# Backplane.net
KiCad netlist of a schematic drawn in Altium Designer
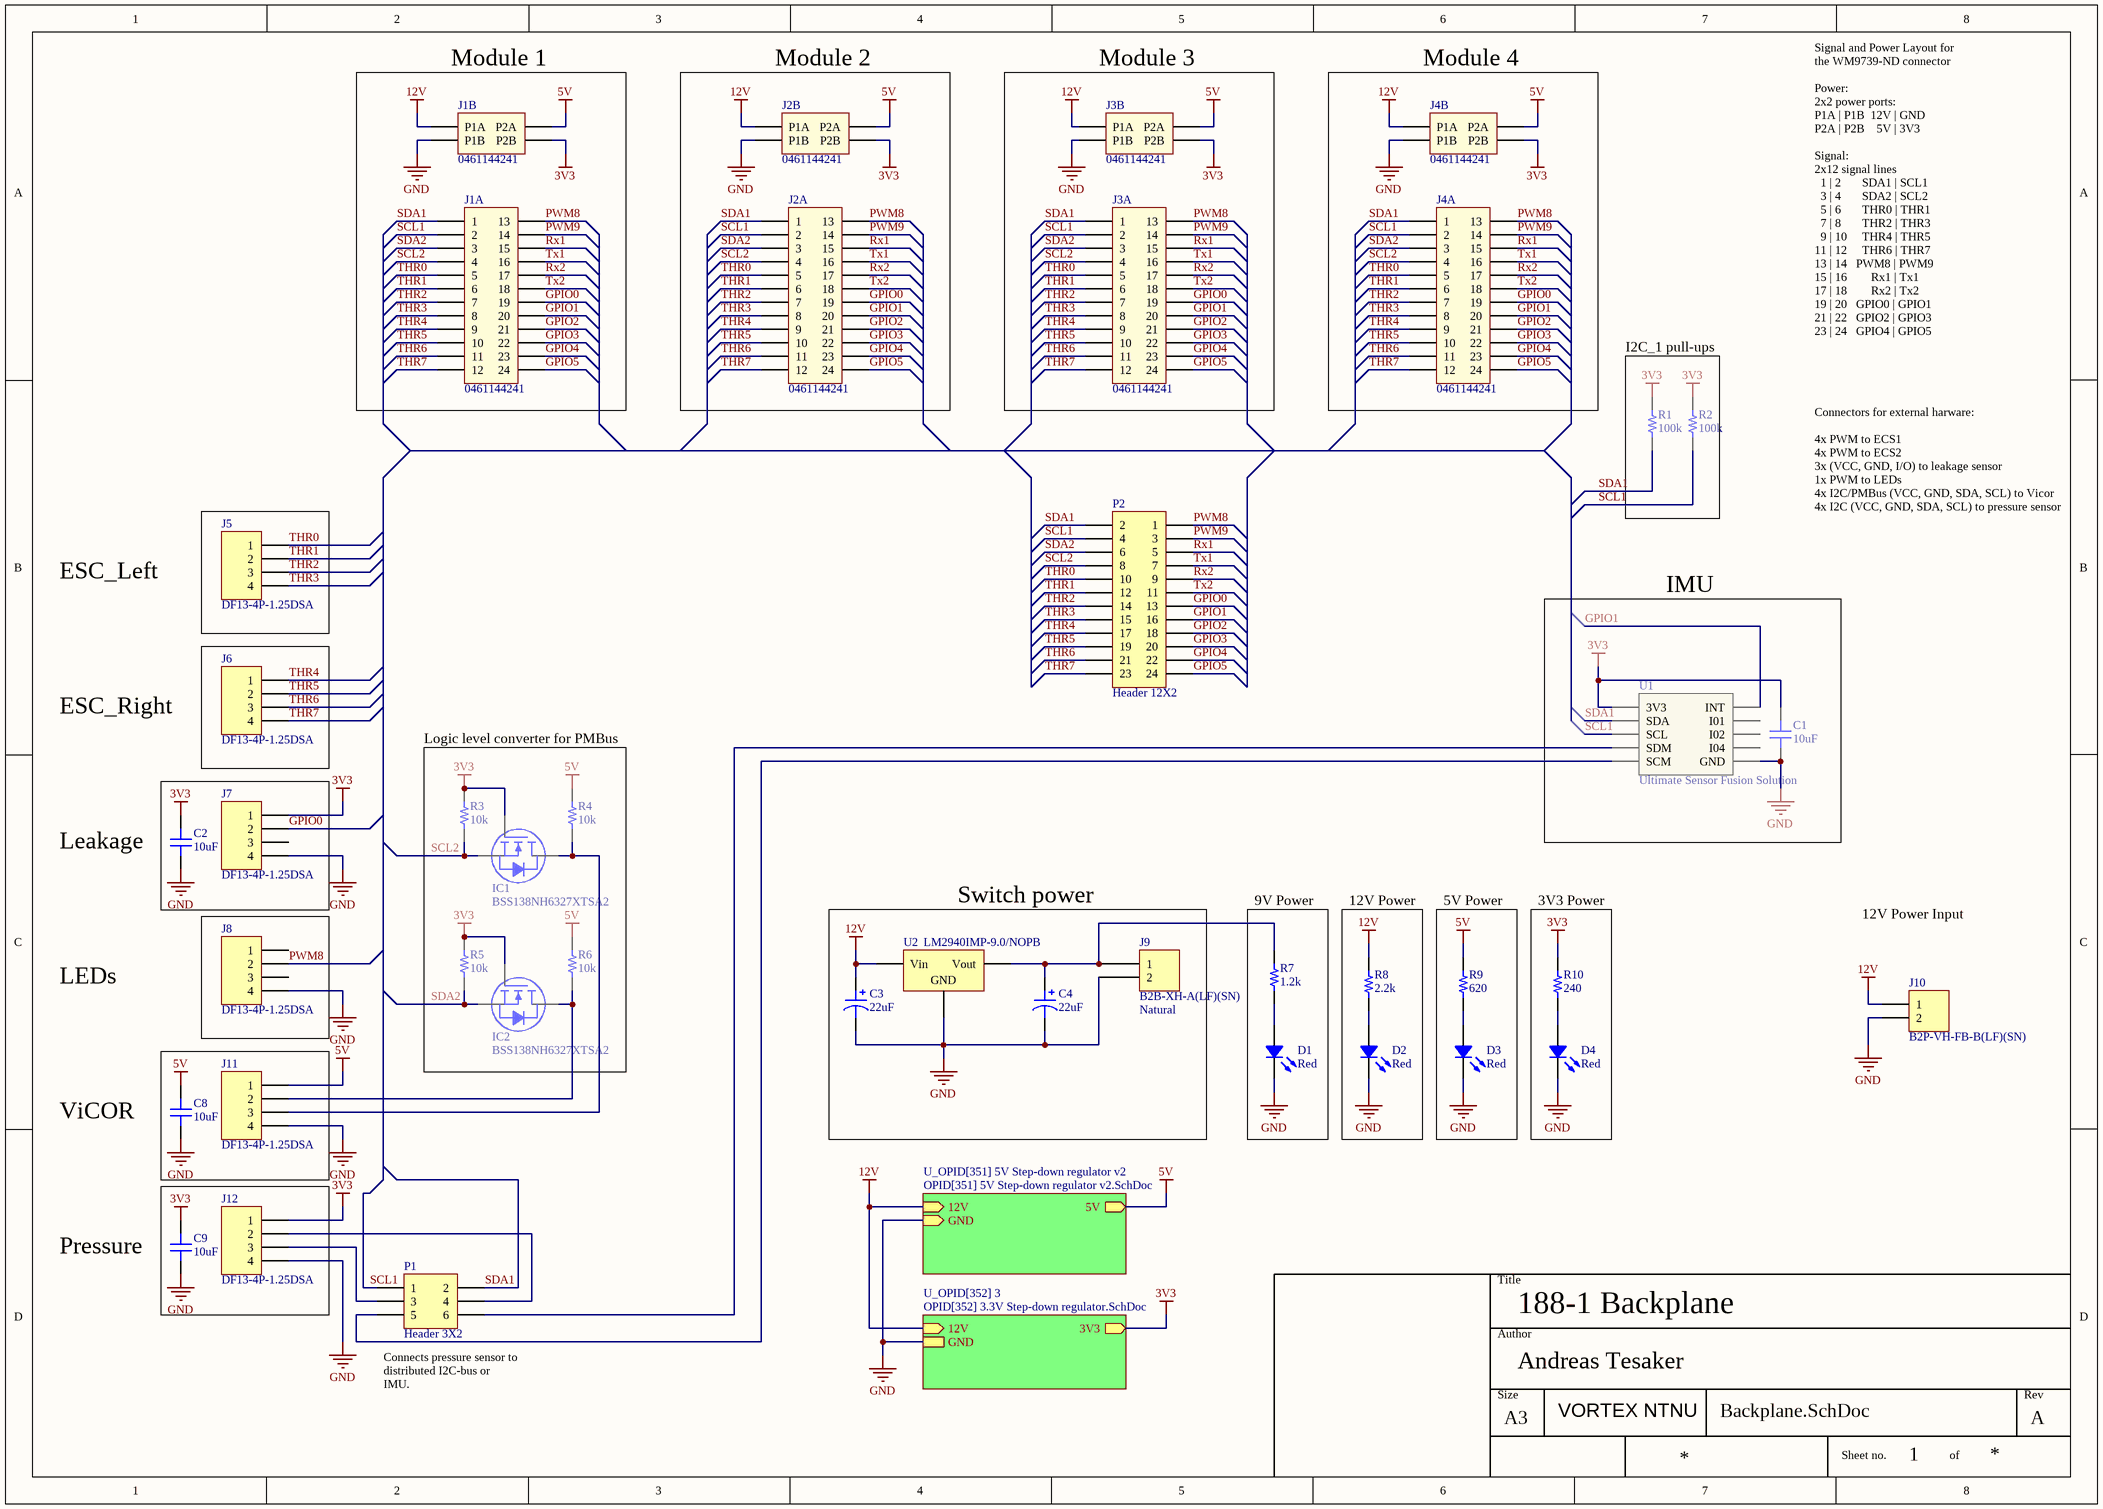
[diagram p0: Backplane.SchDoc]

(export (version "E")
  (design (tool "Eeschema 10.0.6"))
  (components
    (comp (ref "C1")
      (value "10uF")
      (footprint "CAP 1210/3225 - 2.8MM")
      (description "CAP CER 10UF 50V X7S 1210")
      (fields
        (field (name "PART NUMBER") "C3225X7S1H106M250AB")
        (field (name "MANUFACTURER") "TDK Corporation")
      )
      (libsource (lib "Celestial Library Database") (part "Capacitor"))
    )
    (comp (ref "C2")
      (value "10uF")
      (footprint "CAP 1210/3225 - 2.8MM")
      (description "CAP CER 10UF 50V X7S 1210")
      (fields
        (field (name "PART NUMBER") "C3225X7S1H106M250AB")
        (field (name "MANUFACTURER") "TDK Corporation")
      )
      (libsource (lib "Celestial Library Database") (part "Capacitor"))
    )
    (comp (ref "C3")
      (value "22uF")
      (footprint "CAP ALUM 6.6MM")
      (description "CAP ALUM 22UF 20% 35V SMD")
      (fields (field (name "PART NUMBER") "UWJ1V220MCL1GB") (field (name "MANUFACTURER") "Nichicon"))
      (libsource (lib "Celestial Library Database") (part "Polarised Capacitor"))
    )
    (comp (ref "C4")
      (value "22uF")
      (footprint "CAP POL 2917/7343")
      (description "CAP TANT 22UF 20V 20% 2917")
      (fields (field (name "PART NUMBER") "293D226X0020D2TE3") (field (name "MANUFACTURER") "Vishay Sprague"))
      (libsource (lib "Celestial Library Database") (part "Polarised Capacitor"))
    )
    (comp (ref "C8")
      (value "10uF")
      (footprint "CAP 1210/3225 - 2.8MM")
      (description "CAP CER 10UF 50V X7S 1210")
      (fields
        (field (name "PART NUMBER") "C3225X7S1H106M250AB")
        (field (name "MANUFACTURER") "TDK Corporation")
      )
      (libsource (lib "Celestial Library Database") (part "Capacitor"))
    )
    (comp (ref "C9")
      (value "10uF")
      (footprint "CAP 1210/3225 - 2.8MM")
      (description "CAP CER 10UF 50V X7S 1210")
      (fields
        (field (name "PART NUMBER") "C3225X7S1H106M250AB")
        (field (name "MANUFACTURER") "TDK Corporation")
      )
      (libsource (lib "Celestial Library Database") (part "Capacitor"))
    )
    (comp (ref "D1")
      (value "Red")
      (footprint "LED 0805/2012 RED")
      (description "LED RED DIFFUSED 0805 SMD")
      (fields
        (field (name "PART NUMBER") "LH R974-LP-1")
        (field (name "MANUFACTURER") "OSRAM Opto Semiconductors Inc.")
      )
      (libsource (lib "Celestial Library Database") (part "LED"))
    )
    (comp (ref "D2")
      (value "Red")
      (footprint "LED 0805/2012 RED")
      (description "LED RED DIFFUSED 0805 SMD")
      (fields
        (field (name "PART NUMBER") "LH R974-LP-1")
        (field (name "MANUFACTURER") "OSRAM Opto Semiconductors Inc.")
      )
      (libsource (lib "Celestial Library Database") (part "LED"))
    )
    (comp (ref "D3")
      (value "Red")
      (footprint "LED 0805/2012 RED")
      (description "LED RED DIFFUSED 0805 SMD")
      (fields
        (field (name "PART NUMBER") "LH R974-LP-1")
        (field (name "MANUFACTURER") "OSRAM Opto Semiconductors Inc.")
      )
      (libsource (lib "Celestial Library Database") (part "LED"))
    )
    (comp (ref "D4")
      (value "Red")
      (footprint "LED 0805/2012 RED")
      (description "LED RED DIFFUSED 0805 SMD")
      (fields
        (field (name "PART NUMBER") "LH R974-LP-1")
        (field (name "MANUFACTURER") "OSRAM Opto Semiconductors Inc.")
      )
      (libsource (lib "Celestial Library Database") (part "LED"))
    )
    (comp (ref "IC1")
      (value "BSS138NH6327XTSA2")
      (footprint "INFINEON SOT-23-3")
      (description "MOSFET N-CH 60V 230MA SOT-23")
      (fields (field (name "MANUFACTURER") "Infineon Technologies"))
      (libsource (lib "Celestial Library Database") (part "INFINEON MOSFET N-CH SOT-23-3"))
    )
    (comp (ref "IC2")
      (value "BSS138NH6327XTSA2")
      (footprint "INFINEON SOT-23-3")
      (description "MOSFET N-CH 60V 230MA SOT-23")
      (fields (field (name "MANUFACTURER") "Infineon Technologies"))
      (libsource (lib "Celestial Library Database") (part "INFINEON MOSFET N-CH SOT-23-3"))
    )
    (comp (ref "J1")
      (value "0461144241")
      (footprint "LPH_VERT.RECEPT._ASSY_4PX24S")
      (libsource (lib "Vortex-component-database") (part "LPHPower_connector"))
    )
    (comp (ref "J2")
      (value "0461144241")
      (footprint "LPH_VERT.RECEPT._ASSY_4PX24S")
      (libsource (lib "Vortex-component-database") (part "LPHPower_connector"))
    )
    (comp (ref "J3")
      (value "0461144241")
      (footprint "LPH_VERT.RECEPT._ASSY_4PX24S")
      (libsource (lib "Vortex-component-database") (part "LPHPower_connector"))
    )
    (comp (ref "J4")
      (value "0461144241")
      (footprint "LPH_VERT.RECEPT._ASSY_4PX24S")
      (libsource (lib "Vortex-component-database") (part "LPHPower_connector"))
    )
    (comp (ref "J5")
      (value "DF13-4P-1.25DSA")
      (footprint "HDRV4W35P125_1X4_665X340X430P")
      (libsource (lib "Vortex-component-database") (part "Header 4"))
    )
    (comp (ref "J6")
      (value "DF13-4P-1.25DSA")
      (footprint "HDRV4W35P125_1X4_665X340X430P")
      (libsource (lib "Vortex-component-database") (part "Header 4"))
    )
    (comp (ref "J7")
      (value "DF13-4P-1.25DSA")
      (footprint "HDRV4W35P125_1X4_665X340X430P")
      (libsource (lib "Vortex-component-database") (part "Header 4"))
    )
    (comp (ref "J8")
      (value "DF13-4P-1.25DSA")
      (footprint "HDRV4W35P125_1X4_665X340X430P")
      (libsource (lib "Vortex-component-database") (part "Header 4"))
    )
    (comp (ref "J9")
      (value "B2B-XH-A(LF)(SN)")
      (footprint "JST XH B2B-XH-A")
      (description "CONN HEADER XH TOP 2POS 2.5MM")
      (fields (field (name "COLOUR") "Natural") (field (name "MANUFACTURER") "JST Sales America Inc."))
      (libsource (lib "Celestial Library Database") (part "2 Pin"))
    )
    (comp (ref "J10")
      (value "B2P-VH-FB-B(LF)(SN)")
      (footprint "B2P-VH-FB-B")
      (libsource (lib "Vortex-component-database") (part "Header 2"))
    )
    (comp (ref "J11")
      (value "DF13-4P-1.25DSA")
      (footprint "HDRV4W35P125_1X4_665X340X430P")
      (libsource (lib "Vortex-component-database") (part "Header 4"))
    )
    (comp (ref "J12")
      (value "DF13-4P-1.25DSA")
      (footprint "HDRV4W35P125_1X4_665X340X430P")
      (libsource (lib "Vortex-component-database") (part "Header 4"))
    )
    (comp (ref "P1")
      (value "Header 3X2")
      (footprint "HDR2X3")
      (description "Header, 3-Pin, Dual row")
      (fields (field (name "PUBLISHER") "Altium Limited"))
      (libsource (lib "Miscellaneous Connectors") (part "Header 3X2"))
    )
    (comp (ref "P2")
      (value "Header 12X2")
      (footprint "HDR2X12")
      (description "Header, 12-Pin, Dual row")
      (fields (field (name "PUBLISHER") "Altium Limited"))
      (libsource (lib "Miscellaneous Connectors") (part "Header 12X2"))
    )
    (comp (ref "R1")
      (value "100k")
      (footprint "RES 0805/2012")
      (description "RES SMD 100K OHM 1% 1/8W 0805")
      (fields
        (field (name "PART NUMBER") "ERJ-6ENF1003V")
        (field (name "MANUFACTURER") "Panasonic Electronic Components")
      )
      (libsource (lib "Celestial Library Database") (part "Resistor"))
    )
    (comp (ref "R2")
      (value "100k")
      (footprint "RES 0805/2012")
      (description "RES SMD 100K OHM 1% 1/8W 0805")
      (fields
        (field (name "PART NUMBER") "ERJ-6ENF1003V")
        (field (name "MANUFACTURER") "Panasonic Electronic Components")
      )
      (libsource (lib "Celestial Library Database") (part "Resistor"))
    )
    (comp (ref "R3")
      (value "10k")
      (footprint "RES 0805/2012")
      (description "RES SMD 10K OHM 1% 1/8W 0805")
      (fields
        (field (name "PART NUMBER") "ERJ-6ENF1002V")
        (field (name "MANUFACTURER") "Panasonic Electronic Components")
      )
      (libsource (lib "Celestial Library Database") (part "Resistor"))
    )
    (comp (ref "R4")
      (value "10k")
      (footprint "RES 0805/2012")
      (description "RES SMD 10K OHM 1% 1/8W 0805")
      (fields
        (field (name "PART NUMBER") "ERJ-6ENF1002V")
        (field (name "MANUFACTURER") "Panasonic Electronic Components")
      )
      (libsource (lib "Celestial Library Database") (part "Resistor"))
    )
    (comp (ref "R5")
      (value "10k")
      (footprint "RES 0805/2012")
      (description "RES SMD 10K OHM 1% 1/8W 0805")
      (fields
        (field (name "PART NUMBER") "ERJ-6ENF1002V")
        (field (name "MANUFACTURER") "Panasonic Electronic Components")
      )
      (libsource (lib "Celestial Library Database") (part "Resistor"))
    )
    (comp (ref "R6")
      (value "10k")
      (footprint "RES 0805/2012")
      (description "RES SMD 10K OHM 1% 1/8W 0805")
      (fields
        (field (name "PART NUMBER") "ERJ-6ENF1002V")
        (field (name "MANUFACTURER") "Panasonic Electronic Components")
      )
      (libsource (lib "Celestial Library Database") (part "Resistor"))
    )
    (comp (ref "R7")
      (value "1.2k")
      (footprint "RES 0805/2012")
      (description "RES SMD 1.2K OHM 5% 1/8W 0805")
      (fields
        (field (name "PART NUMBER") "ERJ-6GEYJ122V")
        (field (name "MANUFACTURER") "Panasonic Electronic Components")
      )
      (libsource (lib "Celestial Library Database") (part "Resistor"))
    )
    (comp (ref "R8")
      (value "2.2k")
      (footprint "RES 0805/2012")
      (description "RES SMD 2.2K OHM 0.1% 1/8W 0805")
      (fields
        (field (name "PART NUMBER") "ERA-6AEB222V")
        (field (name "MANUFACTURER") "Panasonic Electronic Components")
      )
      (libsource (lib "Celestial Library Database") (part "Resistor"))
    )
    (comp (ref "R9")
      (value "620")
      (footprint "RES 0805/2012")
      (description "RES SMD 620 OHM 1% 1/8W 0805")
      (fields
        (field (name "PART NUMBER") "ERJ-6ENF6200V")
        (field (name "MANUFACTURER") "Panasonic Electronic Components")
      )
      (libsource (lib "Celestial Library Database") (part "Resistor"))
    )
    (comp (ref "R10")
      (value "240")
      (footprint "RES 0805/2012")
      (description "RES SMD 240 OHM 5% 1/2W 0805")
      (fields
        (field (name "PART NUMBER") "ERJ-P06J241V")
        (field (name "MANUFACTURER") "Panasonic Electronic Components")
      )
      (libsource (lib "Celestial Library Database") (part "Resistor"))
    )
    (comp (ref "U1")
      (value "Ultimate Sensor Fusion Solution")
      (footprint "Ultimate Sensor Fusion Solution")
      (libsource (lib "Vortex-component-database") (part "Ultimate Sensor Fusion Solution"))
    )
    (comp (ref "U2")
      (value "LM2940IMP-9.0/NOPB")
      (footprint "SOT230P700X180-4N")
      (libsource (lib "Vortex-component-database") (part "Volt_Reg"))
    )
  )
  (nets
    (net (code "1") (name "/GPIO0") (class "Default")
      (node (ref "J1") (pin "19") (pinfunction "19_19") (pintype "passive"))
      (node (ref "J2") (pin "19") (pinfunction "19_19") (pintype "passive"))
      (node (ref "J3") (pin "19") (pinfunction "19_19") (pintype "passive"))
      (node (ref "J4") (pin "19") (pinfunction "19_19") (pintype "passive"))
      (node (ref "J7") (pin "2") (pinfunction "2_2") (pintype "passive"))
      (node (ref "P2") (pin "13") (pinfunction "13_13") (pintype "passive"))
    )
    (net (code "2") (name "/GPIO1") (class "Default")
      (node (ref "J1") (pin "20") (pinfunction "20_20") (pintype "passive"))
      (node (ref "J2") (pin "20") (pinfunction "20_20") (pintype "passive"))
      (node (ref "J3") (pin "20") (pinfunction "20_20") (pintype "passive"))
      (node (ref "J4") (pin "20") (pinfunction "20_20") (pintype "passive"))
      (node (ref "P2") (pin "16") (pinfunction "16_16") (pintype "passive"))
      (node (ref "U1") (pin "6") (pinfunction "INT_6") (pintype "passive"))
    )
    (net (code "3") (name "/GPIO2") (class "Default")
      (node (ref "J1") (pin "21") (pinfunction "21_21") (pintype "passive"))
      (node (ref "J2") (pin "21") (pinfunction "21_21") (pintype "passive"))
      (node (ref "J3") (pin "21") (pinfunction "21_21") (pintype "passive"))
      (node (ref "J4") (pin "21") (pinfunction "21_21") (pintype "passive"))
      (node (ref "P2") (pin "18") (pinfunction "18_18") (pintype "passive"))
    )
    (net (code "4") (name "/GPIO3") (class "Default")
      (node (ref "J1") (pin "22") (pinfunction "22_22") (pintype "passive"))
      (node (ref "J2") (pin "22") (pinfunction "22_22") (pintype "passive"))
      (node (ref "J3") (pin "22") (pinfunction "22_22") (pintype "passive"))
      (node (ref "J4") (pin "22") (pinfunction "22_22") (pintype "passive"))
      (node (ref "P2") (pin "20") (pinfunction "20_20") (pintype "passive"))
    )
    (net (code "5") (name "/GPIO4") (class "Default")
      (node (ref "J1") (pin "23") (pinfunction "23_23") (pintype "passive"))
      (node (ref "J2") (pin "23") (pinfunction "23_23") (pintype "passive"))
      (node (ref "J3") (pin "23") (pinfunction "23_23") (pintype "passive"))
      (node (ref "J4") (pin "23") (pinfunction "23_23") (pintype "passive"))
      (node (ref "P2") (pin "22") (pinfunction "22_22") (pintype "passive"))
    )
    (net (code "6") (name "/GPIO5") (class "Default")
      (node (ref "J1") (pin "24") (pinfunction "24_24") (pintype "passive"))
      (node (ref "J2") (pin "24") (pinfunction "24_24") (pintype "passive"))
      (node (ref "J3") (pin "24") (pinfunction "24_24") (pintype "passive"))
      (node (ref "J4") (pin "24") (pinfunction "24_24") (pintype "passive"))
      (node (ref "P2") (pin "24") (pinfunction "24_24") (pintype "passive"))
    )
    (net (code "7") (name "/PWM8") (class "Default")
      (node (ref "J1") (pin "13") (pinfunction "13_13") (pintype "passive"))
      (node (ref "J2") (pin "13") (pinfunction "13_13") (pintype "passive"))
      (node (ref "J3") (pin "13") (pinfunction "13_13") (pintype "passive"))
      (node (ref "J4") (pin "13") (pinfunction "13_13") (pintype "passive"))
      (node (ref "J8") (pin "2") (pinfunction "2_2") (pintype "passive"))
      (node (ref "P2") (pin "1") (pinfunction "1_1") (pintype "passive"))
    )
    (net (code "8") (name "/PWM9") (class "Default")
      (node (ref "J1") (pin "14") (pinfunction "14_14") (pintype "passive"))
      (node (ref "J2") (pin "14") (pinfunction "14_14") (pintype "passive"))
      (node (ref "J3") (pin "14") (pinfunction "14_14") (pintype "passive"))
      (node (ref "J4") (pin "14") (pinfunction "14_14") (pintype "passive"))
      (node (ref "P2") (pin "3") (pinfunction "3_3") (pintype "passive"))
    )
    (net (code "9") (name "/Rx1") (class "Default")
      (node (ref "J1") (pin "15") (pinfunction "15_15") (pintype "passive"))
      (node (ref "J2") (pin "15") (pinfunction "15_15") (pintype "passive"))
      (node (ref "J3") (pin "15") (pinfunction "15_15") (pintype "passive"))
      (node (ref "J4") (pin "15") (pinfunction "15_15") (pintype "passive"))
      (node (ref "P2") (pin "5") (pinfunction "5_5") (pintype "passive"))
    )
    (net (code "10") (name "/Rx2") (class "Default")
      (node (ref "J1") (pin "17") (pinfunction "17_17") (pintype "passive"))
      (node (ref "J2") (pin "17") (pinfunction "17_17") (pintype "passive"))
      (node (ref "J3") (pin "17") (pinfunction "17_17") (pintype "passive"))
      (node (ref "J4") (pin "17") (pinfunction "17_17") (pintype "passive"))
      (node (ref "P2") (pin "9") (pinfunction "9_9") (pintype "passive"))
    )
    (net (code "11") (name "/SCL1") (class "Default")
      (node (ref "J1") (pin "2") (pinfunction "2_2") (pintype "passive"))
      (node (ref "J2") (pin "2") (pinfunction "2_2") (pintype "passive"))
      (node (ref "J3") (pin "2") (pinfunction "2_2") (pintype "passive"))
      (node (ref "J4") (pin "2") (pinfunction "2_2") (pintype "passive"))
      (node (ref "P1") (pin "1") (pinfunction "1_1") (pintype "passive"))
      (node (ref "P2") (pin "4") (pinfunction "4_4") (pintype "passive"))
      (node (ref "R2") (pin "1") (pinfunction "1_1") (pintype "passive"))
      (node (ref "U1") (pin "4") (pinfunction "SCL_4") (pintype "passive"))
    )
    (net (code "12") (name "/SCL2") (class "Default")
      (node (ref "IC1") (pin "3") (pinfunction "S_3") (pintype "passive"))
      (node (ref "J1") (pin "4") (pinfunction "4_4") (pintype "passive"))
      (node (ref "J2") (pin "4") (pinfunction "4_4") (pintype "passive"))
      (node (ref "J3") (pin "4") (pinfunction "4_4") (pintype "passive"))
      (node (ref "J4") (pin "4") (pinfunction "4_4") (pintype "passive"))
      (node (ref "P2") (pin "8") (pinfunction "8_8") (pintype "passive"))
      (node (ref "R3") (pin "2") (pinfunction "2_2") (pintype "passive"))
    )
    (net (code "13") (name "/SDA1") (class "Default")
      (node (ref "J1") (pin "1") (pinfunction "1_1") (pintype "passive"))
      (node (ref "J2") (pin "1") (pinfunction "1_1") (pintype "passive"))
      (node (ref "J3") (pin "1") (pinfunction "1_1") (pintype "passive"))
      (node (ref "J4") (pin "1") (pinfunction "1_1") (pintype "passive"))
      (node (ref "P1") (pin "2") (pinfunction "2_2") (pintype "passive"))
      (node (ref "P2") (pin "2") (pinfunction "2_2") (pintype "passive"))
      (node (ref "R1") (pin "1") (pinfunction "1_1") (pintype "passive"))
      (node (ref "U1") (pin "5") (pinfunction "SDA_5") (pintype "passive"))
    )
    (net (code "14") (name "/SDA2") (class "Default")
      (node (ref "IC2") (pin "3") (pinfunction "S_3") (pintype "passive"))
      (node (ref "J1") (pin "3") (pinfunction "3_3") (pintype "passive"))
      (node (ref "J2") (pin "3") (pinfunction "3_3") (pintype "passive"))
      (node (ref "J3") (pin "3") (pinfunction "3_3") (pintype "passive"))
      (node (ref "J4") (pin "3") (pinfunction "3_3") (pintype "passive"))
      (node (ref "P2") (pin "6") (pinfunction "6_6") (pintype "passive"))
      (node (ref "R5") (pin "2") (pinfunction "2_2") (pintype "passive"))
    )
    (net (code "15") (name "/THR0") (class "Default")
      (node (ref "J1") (pin "5") (pinfunction "5_5") (pintype "passive"))
      (node (ref "J2") (pin "5") (pinfunction "5_5") (pintype "passive"))
      (node (ref "J3") (pin "5") (pinfunction "5_5") (pintype "passive"))
      (node (ref "J4") (pin "5") (pinfunction "5_5") (pintype "passive"))
      (node (ref "J5") (pin "1") (pinfunction "1_1") (pintype "passive"))
      (node (ref "P2") (pin "10") (pinfunction "10_10") (pintype "passive"))
    )
    (net (code "16") (name "/THR1") (class "Default")
      (node (ref "J1") (pin "6") (pinfunction "6_6") (pintype "passive"))
      (node (ref "J2") (pin "6") (pinfunction "6_6") (pintype "passive"))
      (node (ref "J3") (pin "6") (pinfunction "6_6") (pintype "passive"))
      (node (ref "J4") (pin "6") (pinfunction "6_6") (pintype "passive"))
      (node (ref "J5") (pin "2") (pinfunction "2_2") (pintype "passive"))
      (node (ref "P2") (pin "12") (pinfunction "12_12") (pintype "passive"))
    )
    (net (code "17") (name "/THR2") (class "Default")
      (node (ref "J1") (pin "7") (pinfunction "7_7") (pintype "passive"))
      (node (ref "J2") (pin "7") (pinfunction "7_7") (pintype "passive"))
      (node (ref "J3") (pin "7") (pinfunction "7_7") (pintype "passive"))
      (node (ref "J4") (pin "7") (pinfunction "7_7") (pintype "passive"))
      (node (ref "J5") (pin "3") (pinfunction "3_3") (pintype "passive"))
      (node (ref "P2") (pin "14") (pinfunction "14_14") (pintype "passive"))
    )
    (net (code "18") (name "/THR3") (class "Default")
      (node (ref "J1") (pin "8") (pinfunction "8_8") (pintype "passive"))
      (node (ref "J2") (pin "8") (pinfunction "8_8") (pintype "passive"))
      (node (ref "J3") (pin "8") (pinfunction "8_8") (pintype "passive"))
      (node (ref "J4") (pin "8") (pinfunction "8_8") (pintype "passive"))
      (node (ref "J5") (pin "4") (pinfunction "4_4") (pintype "passive"))
      (node (ref "P2") (pin "15") (pinfunction "15_15") (pintype "passive"))
    )
    (net (code "19") (name "/THR4") (class "Default")
      (node (ref "J1") (pin "9") (pinfunction "9_9") (pintype "passive"))
      (node (ref "J2") (pin "9") (pinfunction "9_9") (pintype "passive"))
      (node (ref "J3") (pin "9") (pinfunction "9_9") (pintype "passive"))
      (node (ref "J4") (pin "9") (pinfunction "9_9") (pintype "passive"))
      (node (ref "J6") (pin "1") (pinfunction "1_1") (pintype "passive"))
      (node (ref "P2") (pin "17") (pinfunction "17_17") (pintype "passive"))
    )
    (net (code "20") (name "/THR5") (class "Default")
      (node (ref "J1") (pin "10") (pinfunction "10_10") (pintype "passive"))
      (node (ref "J2") (pin "10") (pinfunction "10_10") (pintype "passive"))
      (node (ref "J3") (pin "10") (pinfunction "10_10") (pintype "passive"))
      (node (ref "J4") (pin "10") (pinfunction "10_10") (pintype "passive"))
      (node (ref "J6") (pin "2") (pinfunction "2_2") (pintype "passive"))
      (node (ref "P2") (pin "19") (pinfunction "19_19") (pintype "passive"))
    )
    (net (code "21") (name "/THR6") (class "Default")
      (node (ref "J1") (pin "11") (pinfunction "11_11") (pintype "passive"))
      (node (ref "J2") (pin "11") (pinfunction "11_11") (pintype "passive"))
      (node (ref "J3") (pin "11") (pinfunction "11_11") (pintype "passive"))
      (node (ref "J4") (pin "11") (pinfunction "11_11") (pintype "passive"))
      (node (ref "J6") (pin "3") (pinfunction "3_3") (pintype "passive"))
      (node (ref "P2") (pin "21") (pinfunction "21_21") (pintype "passive"))
    )
    (net (code "22") (name "/THR7") (class "Default")
      (node (ref "J1") (pin "12") (pinfunction "12_12") (pintype "passive"))
      (node (ref "J2") (pin "12") (pinfunction "12_12") (pintype "passive"))
      (node (ref "J3") (pin "12") (pinfunction "12_12") (pintype "passive"))
      (node (ref "J4") (pin "12") (pinfunction "12_12") (pintype "passive"))
      (node (ref "J6") (pin "4") (pinfunction "4_4") (pintype "passive"))
      (node (ref "P2") (pin "23") (pinfunction "23_23") (pintype "passive"))
    )
    (net (code "23") (name "/Tx1") (class "Default")
      (node (ref "J1") (pin "16") (pinfunction "16_16") (pintype "passive"))
      (node (ref "J2") (pin "16") (pinfunction "16_16") (pintype "passive"))
      (node (ref "J3") (pin "16") (pinfunction "16_16") (pintype "passive"))
      (node (ref "J4") (pin "16") (pinfunction "16_16") (pintype "passive"))
      (node (ref "P2") (pin "7") (pinfunction "7_7") (pintype "passive"))
    )
    (net (code "24") (name "/Tx2") (class "Default")
      (node (ref "J1") (pin "18") (pinfunction "18_18") (pintype "passive"))
      (node (ref "J2") (pin "18") (pinfunction "18_18") (pintype "passive"))
      (node (ref "J3") (pin "18") (pinfunction "18_18") (pintype "passive"))
      (node (ref "J4") (pin "18") (pinfunction "18_18") (pintype "passive"))
      (node (ref "P2") (pin "11") (pinfunction "11_11") (pintype "passive"))
    )
    (net (code "25") (name "3V3") (class "Default")
      (node (ref "C1") (pin "2") (pinfunction "2_2") (pintype "passive"))
      (node (ref "C2") (pin "2") (pinfunction "2_2") (pintype "passive"))
      (node (ref "C9") (pin "2") (pinfunction "2_2") (pintype "passive"))
      (node (ref "IC1") (pin "1") (pinfunction "G_1") (pintype "passive"))
      (node (ref "IC2") (pin "1") (pinfunction "G_1") (pintype "passive"))
      (node (ref "J1") (pin "P2B") (pinfunction "P2B_P2B") (pintype "passive"))
      (node (ref "J12") (pin "1") (pinfunction "1_1") (pintype "passive"))
      (node (ref "J2") (pin "P2B") (pinfunction "P2B_P2B") (pintype "passive"))
      (node (ref "J3") (pin "P2B") (pinfunction "P2B_P2B") (pintype "passive"))
      (node (ref "J4") (pin "P2B") (pinfunction "P2B_P2B") (pintype "passive"))
      (node (ref "J7") (pin "1") (pinfunction "1_1") (pintype "passive"))
      (node (ref "R1") (pin "2") (pinfunction "2_2") (pintype "passive"))
      (node (ref "R10") (pin "2") (pinfunction "2_2") (pintype "passive"))
      (node (ref "R2") (pin "2") (pinfunction "2_2") (pintype "passive"))
      (node (ref "R3") (pin "1") (pinfunction "1_1") (pintype "passive"))
      (node (ref "R5") (pin "1") (pinfunction "1_1") (pintype "passive"))
      (node (ref "U1") (pin "2") (pinfunction "3V3_2") (pintype "passive"))
    )
    (net (code "26") (name "5V") (class "Default")
      (node (ref "C8") (pin "2") (pinfunction "2_2") (pintype "passive"))
      (node (ref "J1") (pin "P2A") (pinfunction "P2A_P2A") (pintype "passive"))
      (node (ref "J11") (pin "1") (pinfunction "1_1") (pintype "passive"))
      (node (ref "J2") (pin "P2A") (pinfunction "P2A_P2A") (pintype "passive"))
      (node (ref "J3") (pin "P2A") (pinfunction "P2A_P2A") (pintype "passive"))
      (node (ref "J4") (pin "P2A") (pinfunction "P2A_P2A") (pintype "passive"))
      (node (ref "R4") (pin "1") (pinfunction "1_1") (pintype "passive"))
      (node (ref "R6") (pin "1") (pinfunction "1_1") (pintype "passive"))
      (node (ref "R9") (pin "2") (pinfunction "2_2") (pintype "passive"))
    )
    (net (code "27") (name "12V") (class "Default")
      (node (ref "C3") (pin "1") (pinfunction "1_1") (pintype "passive"))
      (node (ref "J1") (pin "P1A") (pinfunction "P1A_P1A") (pintype "passive"))
      (node (ref "J10") (pin "1") (pinfunction "1_1") (pintype "passive"))
      (node (ref "J2") (pin "P1A") (pinfunction "P1A_P1A") (pintype "passive"))
      (node (ref "J3") (pin "P1A") (pinfunction "P1A_P1A") (pintype "passive"))
      (node (ref "J4") (pin "P1A") (pinfunction "P1A_P1A") (pintype "passive"))
      (node (ref "R8") (pin "2") (pinfunction "2_2") (pintype "passive"))
      (node (ref "U2") (pin "1") (pinfunction "Vin_1") (pintype "passive"))
    )
    (net (code "28") (name "GND") (class "Default")
      (node (ref "C1") (pin "1") (pinfunction "1_1") (pintype "passive"))
      (node (ref "C2") (pin "1") (pinfunction "1_1") (pintype "passive"))
      (node (ref "C3") (pin "2") (pinfunction "2_2") (pintype "passive"))
      (node (ref "C4") (pin "2") (pinfunction "2_2") (pintype "passive"))
      (node (ref "C8") (pin "1") (pinfunction "1_1") (pintype "passive"))
      (node (ref "C9") (pin "1") (pinfunction "1_1") (pintype "passive"))
      (node (ref "D1") (pin "2") (pinfunction "2_2") (pintype "passive"))
      (node (ref "D2") (pin "2") (pinfunction "2_2") (pintype "passive"))
      (node (ref "D3") (pin "2") (pinfunction "2_2") (pintype "passive"))
      (node (ref "D4") (pin "2") (pinfunction "2_2") (pintype "passive"))
      (node (ref "J1") (pin "P1B") (pinfunction "P1B_P1B") (pintype "passive"))
      (node (ref "J10") (pin "2") (pinfunction "2_2") (pintype "passive"))
      (node (ref "J11") (pin "4") (pinfunction "4_4") (pintype "passive"))
      (node (ref "J12") (pin "4") (pinfunction "4_4") (pintype "passive"))
      (node (ref "J2") (pin "P1B") (pinfunction "P1B_P1B") (pintype "passive"))
      (node (ref "J3") (pin "P1B") (pinfunction "P1B_P1B") (pintype "passive"))
      (node (ref "J4") (pin "P1B") (pinfunction "P1B_P1B") (pintype "passive"))
      (node (ref "J7") (pin "4") (pinfunction "4_4") (pintype "passive"))
      (node (ref "J8") (pin "4") (pinfunction "4_4") (pintype "passive"))
      (node (ref "J9") (pin "2") (pinfunction "2_2") (pintype "passive"))
      (node (ref "U1") (pin "1") (pinfunction "GND_1") (pintype "passive"))
      (node (ref "U2") (pin "2") (pinfunction "GND_2") (pintype "passive"))
    )
    (net (code "29") (name "Net-(D1-Pad1)") (class "Default")
      (node (ref "D1") (pin "1") (pinfunction "1_1") (pintype "passive"))
      (node (ref "R7") (pin "1") (pinfunction "1_1") (pintype "passive"))
    )
    (net (code "30") (name "Net-(D2-Pad1)") (class "Default")
      (node (ref "D2") (pin "1") (pinfunction "1_1") (pintype "passive"))
      (node (ref "R8") (pin "1") (pinfunction "1_1") (pintype "passive"))
    )
    (net (code "31") (name "Net-(D3-Pad1)") (class "Default")
      (node (ref "D3") (pin "1") (pinfunction "1_1") (pintype "passive"))
      (node (ref "R9") (pin "1") (pinfunction "1_1") (pintype "passive"))
    )
    (net (code "32") (name "Net-(D4-Pad1)") (class "Default")
      (node (ref "D4") (pin "1") (pinfunction "1_1") (pintype "passive"))
      (node (ref "R10") (pin "1") (pinfunction "1_1") (pintype "passive"))
    )
    (net (code "33") (name "Net-(IC1-D)") (class "Default")
      (node (ref "IC1") (pin "2") (pinfunction "D_2") (pintype "passive"))
      (node (ref "J11") (pin "3") (pinfunction "3_3") (pintype "passive"))
      (node (ref "R4") (pin "2") (pinfunction "2_2") (pintype "passive"))
    )
    (net (code "34") (name "Net-(IC2-D)") (class "Default")
      (node (ref "IC2") (pin "2") (pinfunction "D_2") (pintype "passive"))
      (node (ref "J11") (pin "2") (pinfunction "2_2") (pintype "passive"))
      (node (ref "R6") (pin "2") (pinfunction "2_2") (pintype "passive"))
    )
    (net (code "35") (name "Net-(J12-Pad2)") (class "Default")
      (node (ref "J12") (pin "2") (pinfunction "2_2") (pintype "passive"))
      (node (ref "P1") (pin "4") (pinfunction "4_4") (pintype "passive"))
    )
    (net (code "36") (name "Net-(J12-Pad3)") (class "Default")
      (node (ref "J12") (pin "3") (pinfunction "3_3") (pintype "passive"))
      (node (ref "P1") (pin "3") (pinfunction "3_3") (pintype "passive"))
    )
    (net (code "37") (name "Net-(U1-SCM)") (class "Default")
      (node (ref "P1") (pin "5") (pinfunction "5_5") (pintype "passive"))
      (node (ref "U1") (pin "9") (pinfunction "SCM_9") (pintype "passive"))
    )
    (net (code "38") (name "Net-(U1-SDM)") (class "Default")
      (node (ref "P1") (pin "6") (pinfunction "6_6") (pintype "passive"))
      (node (ref "U1") (pin "10") (pinfunction "SDM_10") (pintype "passive"))
    )
    (net (code "39") (name "Net-(U2-Vout)") (class "Default")
      (node (ref "C4") (pin "1") (pinfunction "1_1") (pintype "passive"))
      (node (ref "J9") (pin "1") (pinfunction "1_1") (pintype "passive"))
      (node (ref "R7") (pin "2") (pinfunction "2_2") (pintype "passive"))
      (node (ref "U2") (pin "3") (pinfunction "Vout_3") (pintype "passive"))
    )
    (net (code "40") (name "unconnected-(J7-Pad3)") (class "Default")
      (node (ref "J7") (pin "3") (pinfunction "3_3") (pintype "passive"))
    )
    (net (code "41") (name "unconnected-(J8-Pad1)") (class "Default")
      (node (ref "J8") (pin "1") (pinfunction "1_1") (pintype "passive"))
    )
    (net (code "42") (name "unconnected-(J8-Pad3)") (class "Default")
      (node (ref "J8") (pin "3") (pinfunction "3_3") (pintype "passive"))
    )
    (net (code "43") (name "unconnected-(U1-I01-Pad8)") (class "Default")
      (node (ref "U1") (pin "8") (pinfunction "I01_8") (pintype "passive"))
    )
    (net (code "44") (name "unconnected-(U1-I02-Pad3)") (class "Default")
      (node (ref "U1") (pin "3") (pinfunction "I02_3") (pintype "passive"))
    )
    (net (code "45") (name "unconnected-(U1-I04-Pad7)") (class "Default")
      (node (ref "U1") (pin "7") (pinfunction "I04_7") (pintype "passive"))
    )
  )
)
